# design.net
KiCad netlist of a schematic drawn in Altium Designer
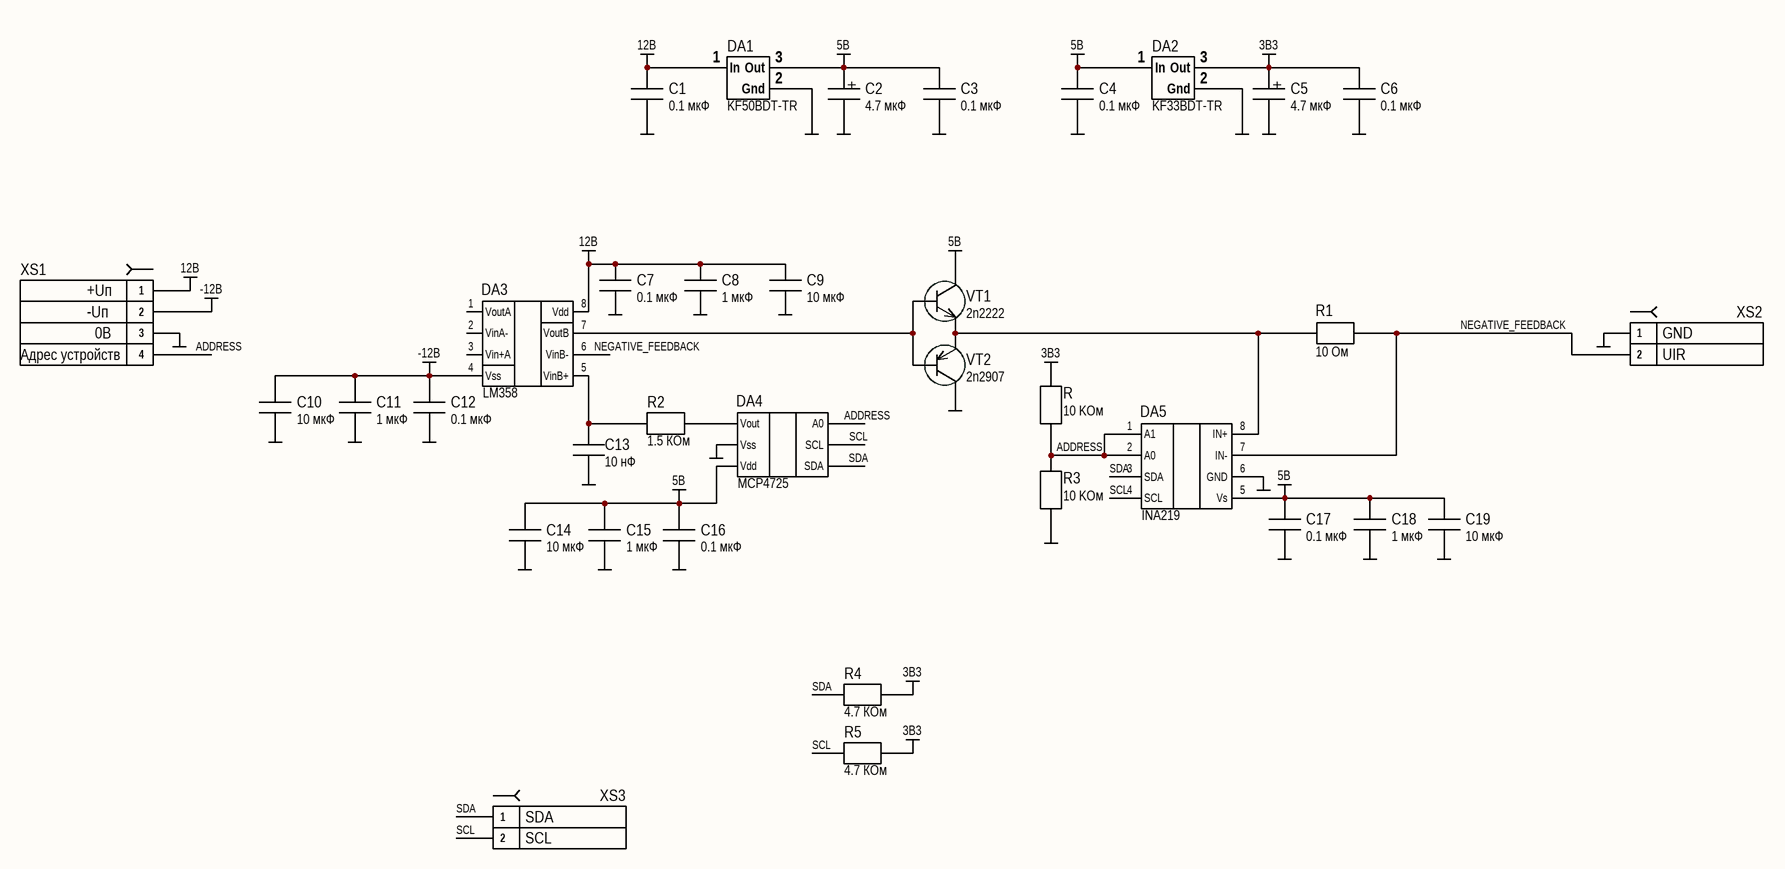
[diagram p0: Схема электрическая принципиальная имитации напряжения, тока и сопротивления.SchDoc]

(export (version "E")
  (design (tool "Eeschema 10.0.6"))
  (components
    (comp (ref "C1")
      (value "0.1 мкФ")
      (footprint "CAP 0603 3D")
      (description "Конденсатор керамика")
      (libsource (lib "RLC V6.4_BVI") (part "C"))
    )
    (comp (ref "C2")
      (value "4.7 мкФ")
      (footprint "Tant A")
      (description "Конденсатор тантал, Тип А")
      (libsource (lib "RLC V6.4_BVI") (part "C T"))
    )
    (comp (ref "C3")
      (value "0.1 мкФ")
      (footprint "CAP 0603 3D")
      (description "Конденсатор керамика")
      (libsource (lib "RLC V6.4_BVI") (part "C"))
    )
    (comp (ref "C4")
      (value "0.1 мкФ")
      (footprint "CAP 0603 3D")
      (description "Конденсатор керамика")
      (libsource (lib "RLC V6.4_BVI") (part "C"))
    )
    (comp (ref "C5")
      (value "4.7 мкФ")
      (footprint "Tant A")
      (description "Конденсатор тантал, Тип А")
      (libsource (lib "RLC V6.4_BVI") (part "C T"))
    )
    (comp (ref "C6")
      (value "0.1 мкФ")
      (footprint "CAP 0603 3D")
      (description "Конденсатор керамика")
      (libsource (lib "RLC V6.4_BVI") (part "C"))
    )
    (comp (ref "C7")
      (value "0.1 мкФ")
      (footprint "CAP 0603 3D")
      (description "Конденсатор керамика")
      (libsource (lib "RLC V6.4_BVI") (part "C"))
    )
    (comp (ref "C8")
      (value "1 мкФ")
      (footprint "CAP 0603 3D")
      (description "Конденсатор керамика")
      (libsource (lib "RLC V6.4_BVI") (part "C"))
    )
    (comp (ref "C9")
      (value "10 мкФ")
      (footprint "cap 1206 3D")
      (description "Конденсатор керамика 1206")
      (libsource (lib "RLC V6.4_BVI") (part "C"))
    )
    (comp (ref "C10")
      (value "10 мкФ")
      (footprint "cap 1206 3D")
      (description "Конденсатор керамика 1206")
      (libsource (lib "RLC V6.4_BVI") (part "C"))
    )
    (comp (ref "C11")
      (value "1 мкФ")
      (footprint "CAP 0603 3D")
      (description "Конденсатор керамика")
      (libsource (lib "RLC V6.4_BVI") (part "C"))
    )
    (comp (ref "C12")
      (value "0.1 мкФ")
      (footprint "CAP 0603 3D")
      (description "Конденсатор керамика")
      (libsource (lib "RLC V6.4_BVI") (part "C"))
    )
    (comp (ref "C13")
      (value "10 нФ")
      (footprint "CAP 0603 3D")
      (description "Конденсатор керамика")
      (libsource (lib "RLC V6.4_BVI") (part "C"))
    )
    (comp (ref "C14")
      (value "10 мкФ")
      (footprint "cap 1206 3D")
      (description "Конденсатор керамика 1206")
      (libsource (lib "RLC V6.4_BVI") (part "C"))
    )
    (comp (ref "C15")
      (value "1 мкФ")
      (footprint "CAP 0603 3D")
      (description "Конденсатор керамика")
      (libsource (lib "RLC V6.4_BVI") (part "C"))
    )
    (comp (ref "C16")
      (value "0.1 мкФ")
      (footprint "CAP 0603 3D")
      (description "Конденсатор керамика")
      (libsource (lib "RLC V6.4_BVI") (part "C"))
    )
    (comp (ref "C17")
      (value "0.1 мкФ")
      (footprint "CAP 0603 3D")
      (description "Конденсатор керамика")
      (libsource (lib "RLC V6.4_BVI") (part "C"))
    )
    (comp (ref "C18")
      (value "1 мкФ")
      (footprint "CAP 0603 3D")
      (description "Конденсатор керамика")
      (libsource (lib "RLC V6.4_BVI") (part "C"))
    )
    (comp (ref "C19")
      (value "10 мкФ")
      (footprint "cap 1206 3D")
      (description "Конденсатор керамика 1206")
      (libsource (lib "RLC V6.4_BVI") (part "C"))
    )
    (comp (ref "DA1")
      (value "KF50BDT-TR")
      (footprint "DPAK")
      (description "Линейный стабилизатор напряжения  5V")
      (libsource (lib "DA V4.8_BVI") (part "MC78Mхх"))
    )
    (comp (ref "DA2")
      (value "KF33BDT-TR")
      (footprint "DPAK")
      (description "Линейный стабилизатор напряжения  5 - 15V")
      (libsource (lib "DA V4.8_BVI") (part "MC78Mхх"))
    )
    (comp (ref "DA3") (value "LM358") (footprint "SOIC-8 150mil") (libsource (lib "LB1") (part "MCP602")))
    (comp (ref "DA4") (value "MCP4725") (footprint "SOT23-6") (libsource (lib "LB1") (part "MCP4725")))
    (comp (ref "DA5") (value "INA219") (footprint "SOP-8") (libsource (lib "LB1") (part "INA219")))
    (comp (ref "R")
      (value "10 KОм")
      (footprint "Res_0603 3D")
      (description "Резисторы плёночные (SMD; МЛТ; С2-33Н; MP9xxx)")
      (libsource (lib "RLC V6.4_BVI") (part "R"))
    )
    (comp (ref "R1")
      (value "10 Ом")
      (footprint "Res_2512 3D")
      (description "Резисторы плёночные (SMD; МЛТ; С2-33Н; MP9xxx), 2512")
      (libsource (lib "RLC V6.4_BVI") (part "R"))
    )
    (comp (ref "R2")
      (value "1.5 КОм")
      (footprint "Res_0603 3D")
      (description "Резисторы плёночные (SMD; МЛТ; С2-33Н; MP9xxx)")
      (libsource (lib "RLC V6.4_BVI") (part "R"))
    )
    (comp (ref "R3")
      (value "10 KОм")
      (footprint "Res_0603 3D")
      (description "Резисторы плёночные (SMD; МЛТ; С2-33Н; MP9xxx)")
      (libsource (lib "RLC V6.4_BVI") (part "R"))
    )
    (comp (ref "R4")
      (value "4.7 КОм")
      (footprint "Res_0603 3D")
      (description "Резисторы плёночные (SMD; МЛТ; С2-33Н; MP9xxx)")
      (libsource (lib "RLC V6.4_BVI") (part "R"))
    )
    (comp (ref "R5")
      (value "4.7 КОм")
      (footprint "Res_0603 3D")
      (description "Резисторы плёночные (SMD; МЛТ; С2-33Н; MP9xxx)")
      (libsource (lib "RLC V6.4_BVI") (part "R"))
    )
    (comp (ref "VT1")
      (value "2n2222")
      (footprint "TO-92 EBC (2)")
      (description "Транзистор NPN")
      (libsource (lib "VD_VT_V5.4 BVI") (part "VT NPN"))
    )
    (comp (ref "VT2")
      (value "2n2907")
      (footprint "TO-92 EBC (2)")
      (description "Транзистор PNP")
      (libsource (lib "VD_VT_V5.4 BVI") (part "VT PNP"))
    )
    (comp (ref "XS1")
      (value "KF-301-4P")
      (footprint "Degson_DG301-5.0-04P-1X")
      (libsource (lib "LB1") (part "KF-301-4P"))
    )
    (comp (ref "XS2")
      (value "KF-301-2P")
      (footprint "Degson_DG301-5.0-02P-1X")
      (libsource (lib "LB1") (part "KF-301-2P"))
    )
    (comp (ref "XS3")
      (value "KF-301-2P")
      (footprint "Degson_DG301-5.0-02P-1X")
      (libsource (lib "LB1") (part "KF-301-2P"))
    )
  )
  (nets
    (net (code "1") (name "-12В") (class "Default")
      (node (ref "C10") (pin "1") (pintype "passive"))
      (node (ref "C11") (pin "2") (pintype "passive"))
      (node (ref "C12") (pin "1") (pintype "passive"))
      (node (ref "DA3") (pin "4") (pinfunction "Vss_4") (pintype "passive"))
      (node (ref "XS1") (pin "2") (pinfunction "2_2") (pintype "passive"))
    )
    (net (code "2") (name "/ADDRESS") (class "Default")
      (node (ref "DA4") (pin "6") (pinfunction "A0_6") (pintype "passive"))
      (node (ref "DA5") (pin "1") (pinfunction "A1_1") (pintype "passive"))
      (node (ref "DA5") (pin "2") (pinfunction "A0_2") (pintype "passive"))
      (node (ref "R") (pin "1") (pintype "passive"))
      (node (ref "R3") (pin "2") (pintype "passive"))
      (node (ref "XS1") (pin "4") (pinfunction "4_4") (pintype "passive"))
    )
    (net (code "3") (name "/NEGATIVE_FEEDBACK") (class "Default")
      (node (ref "DA3") (pin "6") (pinfunction "VinB-_6") (pintype "passive"))
      (node (ref "DA5") (pin "7") (pinfunction "IN-_7") (pintype "passive"))
      (node (ref "R1") (pin "2") (pintype "passive"))
      (node (ref "XS2") (pin "2") (pinfunction "2_2") (pintype "passive"))
    )
    (net (code "4") (name "/SCL") (class "Default")
      (node (ref "DA4") (pin "5") (pinfunction "SCL_5") (pintype "passive"))
      (node (ref "DA5") (pin "4") (pinfunction "SCL_4") (pintype "passive"))
      (node (ref "R5") (pin "1") (pintype "passive"))
      (node (ref "XS3") (pin "2") (pinfunction "2_2") (pintype "passive"))
    )
    (net (code "5") (name "/SDA") (class "Default")
      (node (ref "DA4") (pin "4") (pinfunction "SDA_4") (pintype "passive"))
      (node (ref "DA5") (pin "3") (pinfunction "SDA_3") (pintype "passive"))
      (node (ref "R4") (pin "1") (pintype "passive"))
      (node (ref "XS3") (pin "1") (pinfunction "1_1") (pintype "passive"))
    )
    (net (code "6") (name "3В3") (class "Default")
      (node (ref "C5") (pin "1") (pinfunction "+_1") (pintype "passive"))
      (node (ref "C6") (pin "1") (pintype "passive"))
      (node (ref "DA2") (pin "3") (pinfunction "Out_3") (pintype "passive"))
      (node (ref "R") (pin "2") (pintype "passive"))
      (node (ref "R4") (pin "2") (pintype "passive"))
      (node (ref "R5") (pin "2") (pintype "passive"))
    )
    (net (code "7") (name "5В") (class "Default")
      (node (ref "C14") (pin "1") (pintype "passive"))
      (node (ref "C15") (pin "1") (pintype "passive"))
      (node (ref "C16") (pin "1") (pintype "passive"))
      (node (ref "C17") (pin "1") (pintype "passive"))
      (node (ref "C18") (pin "1") (pintype "passive"))
      (node (ref "C19") (pin "1") (pintype "passive"))
      (node (ref "C2") (pin "1") (pinfunction "+_1") (pintype "passive"))
      (node (ref "C3") (pin "1") (pintype "passive"))
      (node (ref "C4") (pin "1") (pintype "passive"))
      (node (ref "DA1") (pin "3") (pinfunction "Out_3") (pintype "passive"))
      (node (ref "DA2") (pin "1") (pinfunction "In_1") (pintype "passive"))
      (node (ref "DA4") (pin "3") (pinfunction "Vdd_3") (pintype "passive"))
      (node (ref "DA5") (pin "5") (pinfunction "Vs_5") (pintype "passive"))
      (node (ref "VT1") (pin "2") (pinfunction "C_2") (pintype "passive"))
    )
    (net (code "8") (name "12В") (class "Default")
      (node (ref "C1") (pin "2") (pintype "passive"))
      (node (ref "C7") (pin "1") (pintype "passive"))
      (node (ref "C8") (pin "2") (pintype "passive"))
      (node (ref "C9") (pin "1") (pintype "passive"))
      (node (ref "DA1") (pin "1") (pinfunction "In_1") (pintype "passive"))
      (node (ref "DA3") (pin "8") (pinfunction "Vdd_8") (pintype "passive"))
      (node (ref "XS1") (pin "1") (pinfunction "1_1") (pintype "passive"))
    )
    (net (code "9") (name "GND") (class "Default")
      (node (ref "C1") (pin "1") (pintype "passive"))
      (node (ref "C10") (pin "2") (pintype "passive"))
      (node (ref "C11") (pin "1") (pintype "passive"))
      (node (ref "C12") (pin "2") (pintype "passive"))
      (node (ref "C13") (pin "2") (pintype "passive"))
      (node (ref "C14") (pin "2") (pintype "passive"))
      (node (ref "C15") (pin "2") (pintype "passive"))
      (node (ref "C16") (pin "2") (pintype "passive"))
      (node (ref "C17") (pin "2") (pintype "passive"))
      (node (ref "C18") (pin "2") (pintype "passive"))
      (node (ref "C19") (pin "2") (pintype "passive"))
      (node (ref "C2") (pin "2") (pinfunction "-_2") (pintype "passive"))
      (node (ref "C3") (pin "2") (pintype "passive"))
      (node (ref "C4") (pin "2") (pintype "passive"))
      (node (ref "C5") (pin "2") (pinfunction "-_2") (pintype "passive"))
      (node (ref "C6") (pin "2") (pintype "passive"))
      (node (ref "C7") (pin "2") (pintype "passive"))
      (node (ref "C8") (pin "1") (pintype "passive"))
      (node (ref "C9") (pin "2") (pintype "passive"))
      (node (ref "DA1") (pin "2") (pinfunction "Gnd_2") (pintype "passive"))
      (node (ref "DA2") (pin "2") (pinfunction "Gnd_2") (pintype "passive"))
      (node (ref "DA4") (pin "2") (pinfunction "Vss_2") (pintype "passive"))
      (node (ref "DA5") (pin "6") (pinfunction "GND_6") (pintype "passive"))
      (node (ref "R3") (pin "1") (pintype "passive"))
      (node (ref "VT2") (pin "2") (pinfunction "C_2") (pintype "passive"))
      (node (ref "XS1") (pin "3") (pinfunction "3_3") (pintype "passive"))
      (node (ref "XS2") (pin "1") (pinfunction "1_1") (pintype "passive"))
    )
    (net (code "10") (name "Net-(DA3-VinB+)") (class "Default")
      (node (ref "C13") (pin "1") (pintype "passive"))
      (node (ref "DA3") (pin "5") (pinfunction "VinB+_5") (pintype "passive"))
      (node (ref "R2") (pin "1") (pintype "passive"))
    )
    (net (code "11") (name "Net-(DA3-VoutB)") (class "Default")
      (node (ref "DA3") (pin "7") (pinfunction "VoutB_7") (pintype "passive"))
      (node (ref "VT1") (pin "1") (pinfunction "B_1") (pintype "passive"))
      (node (ref "VT2") (pin "1") (pinfunction "B_1") (pintype "passive"))
    )
    (net (code "12") (name "Net-(DA4-Vout)") (class "Default")
      (node (ref "DA4") (pin "1") (pinfunction "Vout_1") (pintype "passive"))
      (node (ref "R2") (pin "2") (pintype "passive"))
    )
    (net (code "13") (name "Net-(DA5-IN+)") (class "Default")
      (node (ref "DA5") (pin "8") (pinfunction "IN+_8") (pintype "passive"))
      (node (ref "R1") (pin "1") (pintype "passive"))
      (node (ref "VT1") (pin "3") (pinfunction "E_3") (pintype "passive"))
      (node (ref "VT2") (pin "3") (pinfunction "E_3") (pintype "passive"))
    )
    (net (code "14") (name "unconnected-(DA3-Vin+A-Pad3)") (class "Default")
      (node (ref "DA3") (pin "3") (pinfunction "Vin+A_3") (pintype "passive"))
    )
    (net (code "15") (name "unconnected-(DA3-VinA--Pad2)") (class "Default")
      (node (ref "DA3") (pin "2") (pinfunction "VinA-_2") (pintype "passive"))
    )
    (net (code "16") (name "unconnected-(DA3-VoutA-Pad1)") (class "Default")
      (node (ref "DA3") (pin "1") (pinfunction "VoutA_1") (pintype "passive"))
    )
  )
)
